# buttons.net
KiCad netlist of a schematic drawn in EAGLE
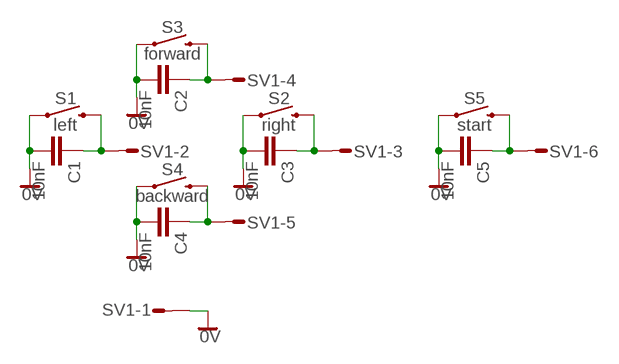
[diagram p0: schematic, sheet 1]

(export (version "E")
  (design (tool "Eeschema 10.0.6"))
  (components
    (comp (ref "C1")
      (value "10nF")
      (footprint "eagle-import:C0805K")
      (libsource (lib "eagle-import") (part "C-EUC0805K"))
    )
    (comp (ref "C2")
      (value "10nF")
      (footprint "eagle-import:C0805K")
      (libsource (lib "eagle-import") (part "C-EUC0805K"))
    )
    (comp (ref "C3")
      (value "10nF")
      (footprint "eagle-import:C0805K")
      (libsource (lib "eagle-import") (part "C-EUC0805K"))
    )
    (comp (ref "C4")
      (value "10nF")
      (footprint "eagle-import:C0805K")
      (libsource (lib "eagle-import") (part "C-EUC0805K"))
    )
    (comp (ref "C5")
      (value "10nF")
      (footprint "eagle-import:C0805K")
      (libsource (lib "eagle-import") (part "C-EUC0805K"))
    )
    (comp (ref "S1")
      (value "left")
      (footprint "eagle-import:TACTILE_SWITCH_SMD_12MM")
      (libsource (lib "eagle-import") (part "MOMENTARY-SWITCH-SPST-SMD-12MM"))
    )
    (comp (ref "S2")
      (value "right")
      (footprint "eagle-import:TACTILE_SWITCH_SMD_12MM")
      (libsource (lib "eagle-import") (part "MOMENTARY-SWITCH-SPST-SMD-12MM"))
    )
    (comp (ref "S3")
      (value "forward")
      (footprint "eagle-import:TACTILE_SWITCH_SMD_12MM")
      (libsource (lib "eagle-import") (part "MOMENTARY-SWITCH-SPST-SMD-12MM"))
    )
    (comp (ref "S4")
      (value "backward")
      (footprint "eagle-import:TACTILE_SWITCH_SMD_12MM")
      (libsource (lib "eagle-import") (part "MOMENTARY-SWITCH-SPST-SMD-12MM"))
    )
    (comp (ref "S5")
      (value "start")
      (footprint "eagle-import:TACTILE_SWITCH_SMD_12MM")
      (libsource (lib "eagle-import") (part "MOMENTARY-SWITCH-SPST-SMD-12MM"))
    )
    (comp (ref "SV1")
      (value "S06P")
      (footprint "eagle-import:S06P")
      (libsource (lib "eagle-import") (part "S06P"))
    )
  )
  (nets
    (net (code "1") (name "0V") (class "Default")
      (node (ref "C1") (pin "2") (pinfunction "2_2") (pintype "passive"))
      (node (ref "C2") (pin "2") (pinfunction "2_2") (pintype "passive"))
      (node (ref "C3") (pin "2") (pinfunction "2_2") (pintype "passive"))
      (node (ref "C4") (pin "2") (pinfunction "2_2") (pintype "passive"))
      (node (ref "C5") (pin "2") (pinfunction "2_2") (pintype "passive"))
      (node (ref "S1") (pin "1") (pinfunction "1_1") (pintype "passive"))
      (node (ref "S2") (pin "1") (pinfunction "1_1") (pintype "passive"))
      (node (ref "S3") (pin "1") (pinfunction "1_1") (pintype "passive"))
      (node (ref "S4") (pin "1") (pinfunction "1_1") (pintype "passive"))
      (node (ref "S5") (pin "1") (pinfunction "1_1") (pintype "passive"))
      (node (ref "SV1") (pin "1") (pinfunction "S_1") (pintype "passive"))
    )
    (net (code "2") (name "Net-(S1-2)") (class "Default")
      (node (ref "C1") (pin "1") (pinfunction "1_1") (pintype "passive"))
      (node (ref "S1") (pin "3") (pinfunction "2_3") (pintype "passive"))
      (node (ref "SV1") (pin "2") (pinfunction "S_2") (pintype "passive"))
    )
    (net (code "3") (name "Net-(S2-2)") (class "Default")
      (node (ref "C3") (pin "1") (pinfunction "1_1") (pintype "passive"))
      (node (ref "S2") (pin "3") (pinfunction "2_3") (pintype "passive"))
      (node (ref "SV1") (pin "3") (pinfunction "S_3") (pintype "passive"))
    )
    (net (code "4") (name "Net-(S3-2)") (class "Default")
      (node (ref "C2") (pin "1") (pinfunction "1_1") (pintype "passive"))
      (node (ref "S3") (pin "3") (pinfunction "2_3") (pintype "passive"))
      (node (ref "SV1") (pin "4") (pinfunction "S_4") (pintype "passive"))
    )
    (net (code "5") (name "Net-(S4-2)") (class "Default")
      (node (ref "C4") (pin "1") (pinfunction "1_1") (pintype "passive"))
      (node (ref "S4") (pin "3") (pinfunction "2_3") (pintype "passive"))
      (node (ref "SV1") (pin "5") (pinfunction "S_5") (pintype "passive"))
    )
    (net (code "6") (name "Net-(S5-2)") (class "Default")
      (node (ref "C5") (pin "1") (pinfunction "1_1") (pintype "passive"))
      (node (ref "S5") (pin "3") (pinfunction "2_3") (pintype "passive"))
      (node (ref "SV1") (pin "6") (pinfunction "S_6") (pintype "passive"))
    )
  )
)
